# sensor_specific.net
KiCad netlist of a schematic drawn in Altium Designer
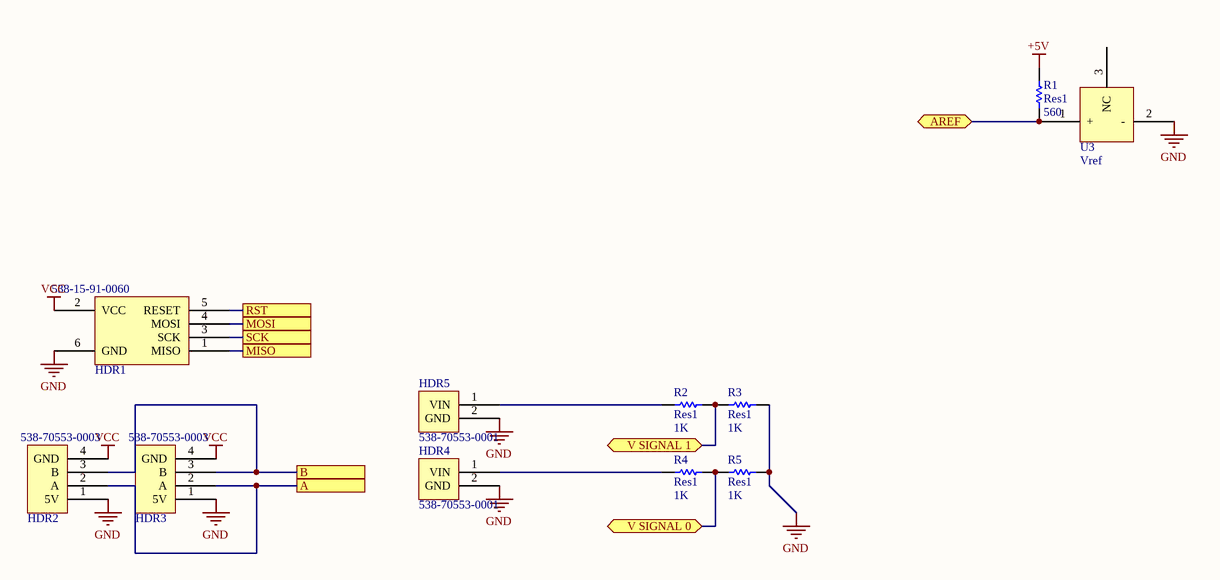
[diagram p0: sensor_specific.SchDoc]

(export (version "E")
  (design (tool "Eeschema 10.0.6"))
  (components
    (comp (ref "HDR1")
      (value "Programming header")
      (footprint "MOLEX_HEADER_6_SMD")
      (fields (field (name "SUPPLIER PART NUMBER 1") "538-15-91-0060"))
      (libsource (lib "Integrated_Library") (part "PRGM_HDR"))
    )
    (comp (ref "HDR2")
      (value "RS-485 interface")
      (footprint "MOLEX_HEADER_4H_SHRD")
      (description "Part Number: 70553-0003. MABSS connector")
      (fields (field (name "SUPPLIER PART NUMBER 1") "538-70553-0003"))
      (libsource (lib "Integrated_Library") (part "MABSS_RS485"))
    )
    (comp (ref "HDR3")
      (value "RS-485 interface")
      (footprint "MOLEX_HEADER_4H_SHRD")
      (description "Part Number: 70553-0003. MABSS connector")
      (fields (field (name "SUPPLIER PART NUMBER 1") "538-70553-0003"))
      (libsource (lib "Integrated_Library") (part "MABSS_RS485"))
    )
    (comp (ref "HDR4")
      (value "MOLEX_HEADER_2H_SHRD")
      (footprint "MOLEX_HEADER_2H_SHRD")
      (description "Part Number: 70553-0001. 2-wire signal inputs")
      (fields (field (name "SUPPLIER PART NUMBER 1") "538-70553-0001"))
      (libsource (lib "Integrated_Library") (part "MOLEX_HEADER_2H_SHRD"))
    )
    (comp (ref "HDR5")
      (value "MOLEX_HEADER_2H_SHRD")
      (footprint "MOLEX_HEADER_2H_SHRD")
      (description "Part Number: 70553-0001. 2-wire signal inputs")
      (fields (field (name "SUPPLIER PART NUMBER 1") "538-70553-0001"))
      (libsource (lib "Integrated_Library") (part "MOLEX_HEADER_2H_SHRD"))
    )
    (comp (ref "R1")
      (value "Res1")
      (footprint "6-0805_N")
      (description "Resistor")
      (fields (field (name "ALTIUM_VALUE") "560") (field (name "PUBLISHER") "Altium Limited"))
      (libsource (lib "Miscellaneous Devices") (part "Res1"))
    )
    (comp (ref "R2")
      (value "Res1")
      (footprint "J1-0603")
      (description "Resistor")
      (fields (field (name "ALTIUM_VALUE") "1K") (field (name "PUBLISHER") "Altium Limited"))
      (libsource (lib "Miscellaneous Devices") (part "Res1"))
    )
    (comp (ref "R3")
      (value "Res1")
      (footprint "J1-0603")
      (description "Resistor")
      (fields (field (name "ALTIUM_VALUE") "1K") (field (name "PUBLISHER") "Altium Limited"))
      (libsource (lib "Miscellaneous Devices") (part "Res1"))
    )
    (comp (ref "R4")
      (value "Res1")
      (footprint "J1-0603")
      (description "Resistor")
      (fields (field (name "ALTIUM_VALUE") "1K") (field (name "PUBLISHER") "Altium Limited"))
      (libsource (lib "Miscellaneous Devices") (part "Res1"))
    )
    (comp (ref "R5")
      (value "Res1")
      (footprint "J1-0603")
      (description "Resistor")
      (fields (field (name "ALTIUM_VALUE") "1K") (field (name "PUBLISHER") "Altium Limited"))
      (libsource (lib "Miscellaneous Devices") (part "Res1"))
    )
    (comp (ref "U3") (value "Vref") (footprint "SOT23_N") (libsource (lib "MABSS") (part "Vref")))
  )
  (nets
    (net (code "1") (name "+5V") (class "Default")
      (node (ref "R1") (pin "2") (pinfunction "2_2") (pintype "passive"))
    )
    (net (code "2") (name "/A") (class "Default")
      (node (ref "HDR2") (pin "2") (pinfunction "A_2") (pintype "passive"))
      (node (ref "HDR3") (pin "2") (pinfunction "A_2") (pintype "passive"))
    )
    (net (code "3") (name "/AREF") (class "Default")
      (node (ref "R1") (pin "1") (pinfunction "1_1") (pintype "passive"))
      (node (ref "U3") (pin "1") (pinfunction "+_1") (pintype "passive"))
    )
    (net (code "4") (name "/B") (class "Default")
      (node (ref "HDR2") (pin "3") (pinfunction "B_3") (pintype "passive"))
      (node (ref "HDR3") (pin "3") (pinfunction "B_3") (pintype "passive"))
    )
    (net (code "5") (name "/MISO") (class "Default")
      (node (ref "HDR1") (pin "1") (pinfunction "MISO_1") (pintype "passive"))
    )
    (net (code "6") (name "/MOSI") (class "Default")
      (node (ref "HDR1") (pin "4") (pinfunction "MOSI_4") (pintype "passive"))
    )
    (net (code "7") (name "/RST") (class "Default")
      (node (ref "HDR1") (pin "5") (pinfunction "RESET_5") (pintype "passive"))
    )
    (net (code "8") (name "/SCK") (class "Default")
      (node (ref "HDR1") (pin "3") (pinfunction "SCK_3") (pintype "passive"))
    )
    (net (code "9") (name "/V SIGNAL 0") (class "Default")
      (node (ref "R4") (pin "2") (pinfunction "2_2") (pintype "passive"))
      (node (ref "R5") (pin "1") (pinfunction "1_1") (pintype "passive"))
    )
    (net (code "10") (name "/V SIGNAL 1") (class "Default")
      (node (ref "R2") (pin "2") (pinfunction "2_2") (pintype "passive"))
      (node (ref "R3") (pin "1") (pinfunction "1_1") (pintype "passive"))
    )
    (net (code "11") (name "GND") (class "Default")
      (node (ref "HDR1") (pin "6") (pinfunction "GND_6") (pintype "passive"))
      (node (ref "HDR2") (pin "1") (pinfunction "5V_1") (pintype "passive"))
      (node (ref "HDR3") (pin "1") (pinfunction "5V_1") (pintype "passive"))
      (node (ref "HDR4") (pin "2") (pinfunction "GND_2") (pintype "passive"))
      (node (ref "HDR5") (pin "2") (pinfunction "GND_2") (pintype "passive"))
      (node (ref "R3") (pin "2") (pinfunction "2_2") (pintype "passive"))
      (node (ref "R5") (pin "2") (pinfunction "2_2") (pintype "passive"))
      (node (ref "U3") (pin "2") (pinfunction "-_2") (pintype "passive"))
    )
    (net (code "12") (name "Net-(HDR4-VIN)") (class "Default")
      (node (ref "HDR4") (pin "1") (pinfunction "VIN_1") (pintype "passive"))
      (node (ref "R4") (pin "1") (pinfunction "1_1") (pintype "passive"))
    )
    (net (code "13") (name "Net-(HDR5-VIN)") (class "Default")
      (node (ref "HDR5") (pin "1") (pinfunction "VIN_1") (pintype "passive"))
      (node (ref "R2") (pin "1") (pinfunction "1_1") (pintype "passive"))
    )
    (net (code "14") (name "VCC") (class "Default")
      (node (ref "HDR1") (pin "2") (pinfunction "VCC_2") (pintype "passive"))
      (node (ref "HDR2") (pin "4") (pinfunction "GND_4") (pintype "passive"))
      (node (ref "HDR3") (pin "4") (pinfunction "GND_4") (pintype "passive"))
    )
    (net (code "15") (name "unconnected-(U3-NC-Pad3)") (class "Default")
      (node (ref "U3") (pin "3") (pinfunction "NC_3") (pintype "passive"))
    )
  )
)
